# CPU.net
KiCad netlist of a schematic drawn in Altium Designer
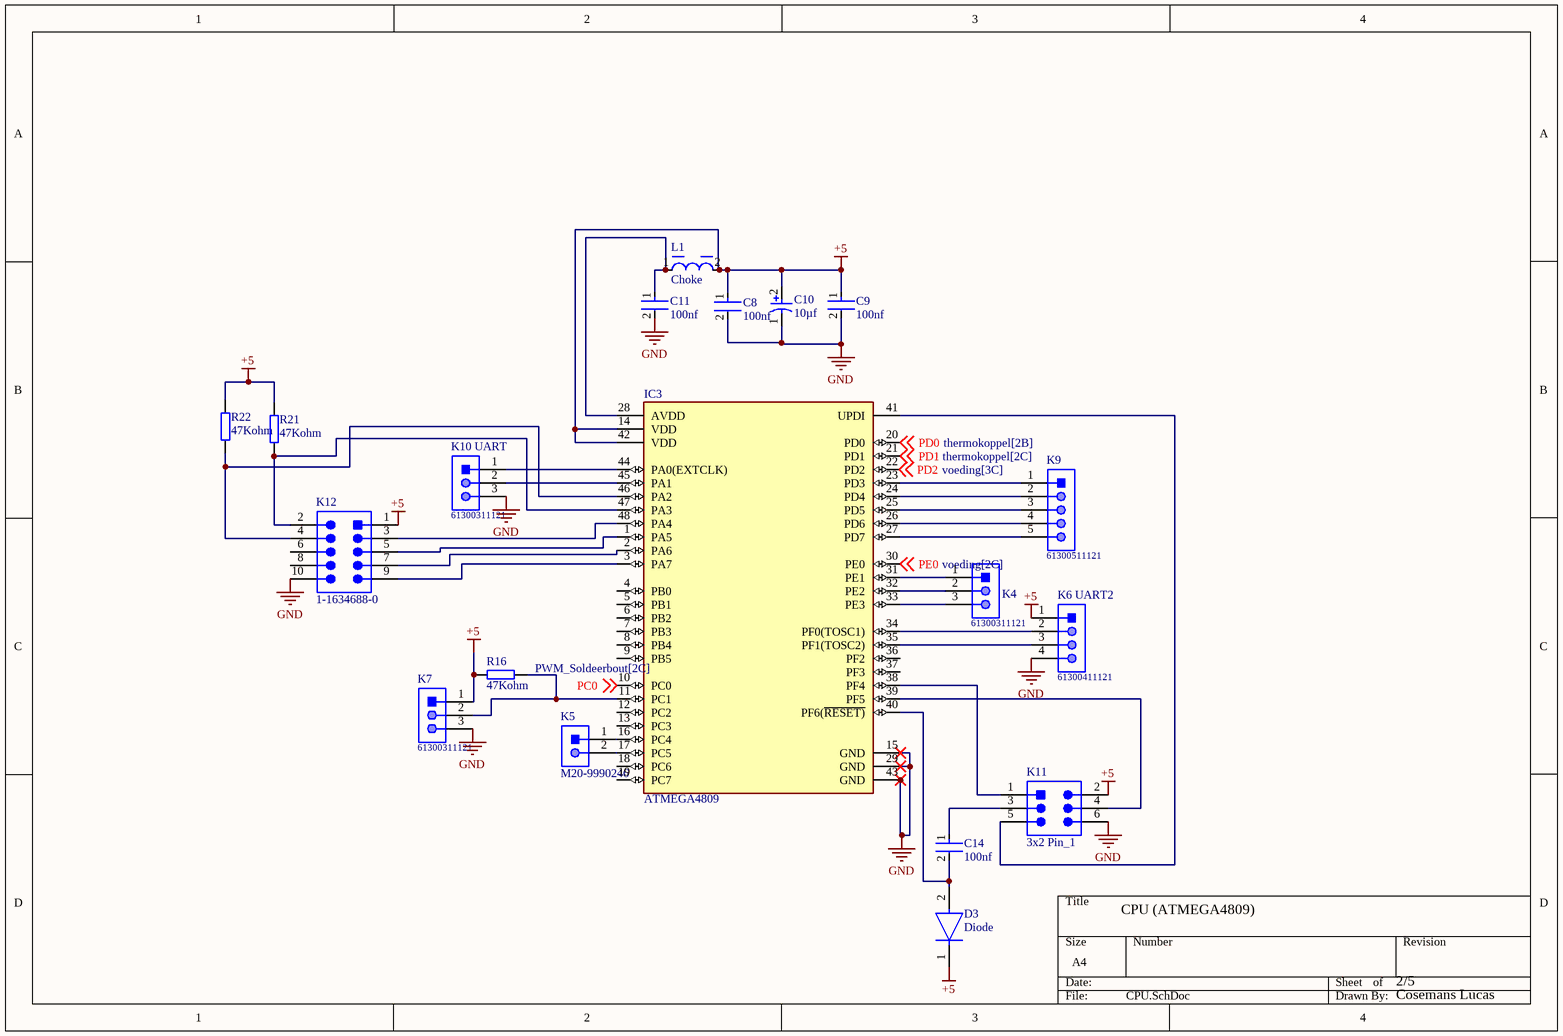
[diagram p0: CPU.SchDoc]

(export (version "E")
  (design (tool "Eeschema 10.0.6"))
  (components
    (comp (ref "C8")
      (value "100nf")
      (footprint "CC_0805_L")
      (fields
        (field (name "MANUFACTURER") "KEMET")
        (field (name "OCTOPART") "https://octopart.com/c0805c224k5ractu-kemet-144670")
        (field (name "MANUFACTURER PART NUMBER") "C0805C224K5RACTU")
      )
      (libsource (lib "Schematic_soldeerstation") (part "Capacitor_Ceramic"))
    )
    (comp (ref "C9")
      (value "100nf")
      (footprint "CC_0805_L")
      (fields
        (field (name "MANUFACTURER") "KEMET")
        (field (name "OCTOPART") "https://octopart.com/c0805c224k5ractu-kemet-144670")
        (field (name "MANUFACTURER PART NUMBER") "C0805C224K5RACTU")
      )
      (libsource (lib "Schematic_soldeerstation") (part "Capacitor_Ceramic"))
    )
    (comp (ref "C10")
      (value "10µf")
      (footprint "CE_D6,3_L4,5")
      (fields (field (name "MANUFACTURER") "Panasonic"))
      (libsource (lib "Schematic_soldeerstation") (part "Capacitor_Electrolytic"))
    )
    (comp (ref "C11")
      (value "100nf")
      (footprint "CC_0805_L")
      (fields
        (field (name "MANUFACTURER") "KEMET")
        (field (name "OCTOPART") "https://octopart.com/c0805c224k5ractu-kemet-144670")
        (field (name "MANUFACTURER PART NUMBER") "C0805C224K5RACTU")
      )
      (libsource (lib "Schematic_soldeerstation") (part "Capacitor_Ceramic"))
    )
    (comp (ref "C14")
      (value "100nf")
      (footprint "CC_0805_L")
      (fields
        (field (name "MANUFACTURER") "KEMET")
        (field (name "OCTOPART") "https://octopart.com/c0805c224k5ractu-kemet-144670")
        (field (name "MANUFACTURER PART NUMBER") "C0805C224K5RACTU")
      )
      (libsource (lib "Schematic_soldeerstation") (part "Capacitor_Ceramic"))
    )
    (comp (ref "D3")
      (value "Diode")
      (footprint "SOD-123FL")
      (fields
        (field (name "MANUFACTURER PART NUMBER") "1N4007")
        (field (name "MANUFACTURER") "Diotec")
        (field (name "OCTOPART") "https://octopart.com/1n4007-diotec-4040411")
      )
      (libsource (lib "Schematic_soldeerstation") (part "Diode"))
    )
    (comp (ref "IC3")
      (value "ATMEGA4809")
      (footprint "TQFP_48_M")
      (libsource (lib "Schematic_soldeerstation") (part "ATMEGA4809"))
    )
    (comp (ref "K4")
      (value "61300311121")
      (footprint "3x1 pin")
      (description "THT Vertical Pin Header WR-PHD, Pitch 2.54 mm, Single Row, 3 pins")
      (fields (field (name "MANUFACTURER") "Wurth Elektronik") (field (name "PUBLISHER") "WurthElektronik"))
      (libsource (lib "") (part "3x1 pin_1"))
    )
    (comp (ref "K5")
      (value "M20-9990246")
      (footprint "2x1 pin")
      (description "CONN HEADER VERT 2POS 2.54MM")
      (fields
        (field (name "OCTOPART") "https://octopart.com/m20-9990246-harwin-2590635")
        (field (name "MANUFACTURER") "Harwin")
      )
      (libsource (lib "Schematic_soldeerstation") (part "2x1 pin"))
    )
    (comp (ref "K6 UART2")
      (value "61300411121")
      (footprint "4x1 pin")
      (description "THT Vertical Pin Header WR-PHD, Pitch 2.54 mm, Single Row, 4 pins")
      (fields (field (name "MANUFACTURER") "Wurth Elektronik") (field (name "PUBLISHER") "WurthElektronik"))
      (libsource (lib "Schematic_soldeerstation") (part "4x1 pin"))
    )
    (comp (ref "K7")
      (value "61300311121")
      (footprint "3x1 pin")
      (description "THT Vertical Pin Header WR-PHD, Pitch 2.54 mm, Single Row, 3 pins")
      (fields (field (name "MANUFACTURER") "Wurth Elektronik") (field (name "PUBLISHER") "WurthElektronik"))
      (libsource (lib "Schematic_soldeerstation") (part "3x1 pin"))
    )
    (comp (ref "K9")
      (value "61300511121")
      (footprint "5x1 pin")
      (description "THT Vertical Pin Header WR-PHD, Pitch 2.54 mm, Single Row, 5 pins")
      (fields (field (name "MANUFACTURER") "Wurth Elektronik") (field (name "PUBLISHER") "WurthElektronik"))
      (libsource (lib "Schematic_soldeerstation") (part "5x1 pin"))
    )
    (comp (ref "K10 UART")
      (value "61300311121")
      (footprint "3x1 pin")
      (description "THT Vertical Pin Header WR-PHD, Pitch 2.54 mm, Single Row, 3 pins")
      (fields (field (name "MANUFACTURER") "Wurth Elektronik") (field (name "PUBLISHER") "WurthElektronik"))
      (libsource (lib "Schematic_soldeerstation") (part "3x1 pin"))
    )
    (comp (ref "K11")
      (value "3x2 Pin_1")
      (footprint "3x2 pin FP-M20-9980346-MFG")
      (libsource (lib "Schematic_soldeerstation") (part "3x2 Pin_1"))
    )
    (comp (ref "K12")
      (value "1-1634688-0")
      (footprint "5x2 pin - TECO-1-1634688-0-10_V")
      (fields (field (name "MANUFACTURER") "TE Connectivity"))
      (libsource (lib "Schematic_soldeerstation") (part "5x2 Pin"))
    )
    (comp (ref "L1")
      (value "Choke")
      (footprint "CC_0805_L")
      (fields (field (name "TOLERANCE") "20%"))
      (libsource (lib "Schematic_soldeerstation") (part "Choke"))
    )
    (comp (ref "R16")
      (value "47Kohm")
      (footprint "R_0805_M")
      (fields (field (name "MANUFACTURER") "Vishay Dale") (field (name "PART NUMBER") "CRCW08050000Z0EA"))
      (libsource (lib "Schematic_soldeerstation") (part "Resistor"))
    )
    (comp (ref "R21")
      (value "47Kohm")
      (footprint "R_0805_M")
      (fields (field (name "MANUFACTURER") "Vishay Dale") (field (name "PART NUMBER") "CRCW08050000Z0EA"))
      (libsource (lib "Schematic_soldeerstation") (part "Resistor"))
    )
    (comp (ref "R22")
      (value "47Kohm")
      (footprint "R_0805_M")
      (fields (field (name "MANUFACTURER") "Vishay Dale") (field (name "PART NUMBER") "CRCW08050000Z0EA"))
      (libsource (lib "Schematic_soldeerstation") (part "Resistor"))
    )
  )
  (nets
    (net (code "1") (name "+5") (class "Default")
      (node (ref "C10") (pin "2") (pinfunction "2_2") (pintype "passive"))
      (node (ref "C8") (pin "1") (pinfunction "1_1") (pintype "passive"))
      (node (ref "C9") (pin "1") (pinfunction "1_1") (pintype "passive"))
      (node (ref "D3") (pin "1") (pinfunction "C_1") (pintype "passive"))
      (node (ref "IC3") (pin "14") (pinfunction "VDD_14") (pintype "power_in"))
      (node (ref "IC3") (pin "42") (pinfunction "VDD_42") (pintype "power_in"))
      (node (ref "K11") (pin "2") (pinfunction "2_2") (pintype "passive"))
      (node (ref "K12") (pin "1") (pinfunction "1_1") (pintype "passive"))
      (node (ref "K6 UART2") (pin "1") (pinfunction "1_1") (pintype "passive"))
      (node (ref "K7") (pin "1") (pinfunction "1_1") (pintype "passive"))
      (node (ref "L1") (pin "2") (pinfunction "2_2") (pintype "passive"))
      (node (ref "R16") (pin "1") (pinfunction "1_1") (pintype "passive"))
      (node (ref "R21") (pin "1") (pinfunction "1_1") (pintype "passive"))
      (node (ref "R22") (pin "1") (pinfunction "1_1") (pintype "passive"))
    )
    (net (code "2") (name "GND") (class "Default")
      (node (ref "C10") (pin "1") (pinfunction "1_1") (pintype "passive"))
      (node (ref "C11") (pin "2") (pinfunction "2_2") (pintype "passive"))
      (node (ref "C8") (pin "2") (pinfunction "2_2") (pintype "passive"))
      (node (ref "C9") (pin "2") (pinfunction "2_2") (pintype "passive"))
      (node (ref "IC3") (pin "15") (pinfunction "GND_15") (pintype "open_emitter"))
      (node (ref "IC3") (pin "29") (pinfunction "GND_29") (pintype "power_in"))
      (node (ref "IC3") (pin "43") (pinfunction "GND_43") (pintype "power_in"))
      (node (ref "K10 UART") (pin "3") (pinfunction "3_3") (pintype "passive"))
      (node (ref "K11") (pin "6") (pinfunction "6_6") (pintype "passive"))
      (node (ref "K12") (pin "10") (pinfunction "10_10") (pintype "passive"))
      (node (ref "K6 UART2") (pin "4") (pinfunction "4_4") (pintype "passive"))
      (node (ref "K7") (pin "3") (pinfunction "3_3") (pintype "passive"))
    )
    (net (code "3") (name "Net-(C14-Pad1)") (class "Default")
      (node (ref "C14") (pin "1") (pinfunction "1_1") (pintype "passive"))
      (node (ref "K11") (pin "3") (pinfunction "3_3") (pintype "passive"))
    )
    (net (code "4") (name "Net-(D3-A)") (class "Default")
      (node (ref "C14") (pin "2") (pinfunction "2_2") (pintype "passive"))
      (node (ref "D3") (pin "2") (pinfunction "A_2") (pintype "passive"))
      (node (ref "IC3") (pin "40") (pinfunction "PF6(~{RESET)}_40") (pintype "bidirectional"))
    )
    (net (code "5") (name "Net-(IC3-AVDD)") (class "Default")
      (node (ref "C11") (pin "1") (pinfunction "1_1") (pintype "passive"))
      (node (ref "IC3") (pin "28") (pinfunction "AVDD_28") (pintype "power_in"))
      (node (ref "L1") (pin "1") (pinfunction "1_1") (pintype "passive"))
    )
    (net (code "6") (name "Net-(IC3-PA0(EXTCLK))") (class "Default")
      (node (ref "IC3") (pin "44") (pinfunction "PA0(EXTCLK)_44") (pintype "bidirectional"))
      (node (ref "K10 UART") (pin "1") (pinfunction "1_1") (pintype "passive"))
    )
    (net (code "7") (name "Net-(IC3-PA1)") (class "Default")
      (node (ref "IC3") (pin "45") (pinfunction "PA1_45") (pintype "bidirectional"))
      (node (ref "K10 UART") (pin "2") (pinfunction "2_2") (pintype "passive"))
    )
    (net (code "8") (name "Net-(IC3-PA2)") (class "Default")
      (node (ref "IC3") (pin "46") (pinfunction "PA2_46") (pintype "bidirectional"))
      (node (ref "K12") (pin "4") (pinfunction "4_4") (pintype "passive"))
      (node (ref "R22") (pin "2") (pinfunction "2_2") (pintype "passive"))
    )
    (net (code "9") (name "Net-(IC3-PA3)") (class "Default")
      (node (ref "IC3") (pin "47") (pinfunction "PA3_47") (pintype "bidirectional"))
      (node (ref "K12") (pin "2") (pinfunction "2_2") (pintype "passive"))
      (node (ref "R21") (pin "2") (pinfunction "2_2") (pintype "passive"))
    )
    (net (code "10") (name "Net-(IC3-PA4)") (class "Default")
      (node (ref "IC3") (pin "48") (pinfunction "PA4_48") (pintype "bidirectional"))
      (node (ref "K12") (pin "3") (pinfunction "3_3") (pintype "passive"))
    )
    (net (code "11") (name "Net-(IC3-PA5)") (class "Default")
      (node (ref "IC3") (pin "1") (pinfunction "PA5_1") (pintype "bidirectional"))
      (node (ref "K12") (pin "5") (pinfunction "5_5") (pintype "passive"))
    )
    (net (code "12") (name "Net-(IC3-PA6)") (class "Default")
      (node (ref "IC3") (pin "2") (pinfunction "PA6_2") (pintype "bidirectional"))
      (node (ref "K12") (pin "7") (pinfunction "7_7") (pintype "passive"))
    )
    (net (code "13") (name "Net-(IC3-PA7)") (class "Default")
      (node (ref "IC3") (pin "3") (pinfunction "PA7_3") (pintype "bidirectional"))
      (node (ref "K12") (pin "9") (pinfunction "9_9") (pintype "passive"))
    )
    (net (code "14") (name "Net-(IC3-PC1)") (class "Default")
      (node (ref "IC3") (pin "11") (pinfunction "PC1_11") (pintype "bidirectional"))
      (node (ref "K7") (pin "2") (pinfunction "2_2") (pintype "passive"))
      (node (ref "R16") (pin "2") (pinfunction "2_2") (pintype "passive"))
    )
    (net (code "15") (name "Net-(IC3-PC4)") (class "Default")
      (node (ref "IC3") (pin "16") (pinfunction "PC4_16") (pintype "bidirectional"))
      (node (ref "K5") (pin "1") (pinfunction "1_1") (pintype "passive"))
    )
    (net (code "16") (name "Net-(IC3-PC5)") (class "Default")
      (node (ref "IC3") (pin "17") (pinfunction "PC5_17") (pintype "bidirectional"))
      (node (ref "K5") (pin "2") (pinfunction "2_2") (pintype "passive"))
    )
    (net (code "17") (name "Net-(IC3-PD3)") (class "Default")
      (node (ref "IC3") (pin "23") (pinfunction "PD3_23") (pintype "bidirectional"))
      (node (ref "K9") (pin "1") (pinfunction "1_1") (pintype "passive"))
    )
    (net (code "18") (name "Net-(IC3-PD4)") (class "Default")
      (node (ref "IC3") (pin "24") (pinfunction "PD4_24") (pintype "bidirectional"))
      (node (ref "K9") (pin "2") (pinfunction "2_2") (pintype "passive"))
    )
    (net (code "19") (name "Net-(IC3-PD5)") (class "Default")
      (node (ref "IC3") (pin "25") (pinfunction "PD5_25") (pintype "bidirectional"))
      (node (ref "K9") (pin "3") (pinfunction "3_3") (pintype "passive"))
    )
    (net (code "20") (name "Net-(IC3-PD6)") (class "Default")
      (node (ref "IC3") (pin "26") (pinfunction "PD6_26") (pintype "bidirectional"))
      (node (ref "K9") (pin "4") (pinfunction "4_4") (pintype "passive"))
    )
    (net (code "21") (name "Net-(IC3-PD7)") (class "Default")
      (node (ref "IC3") (pin "27") (pinfunction "PD7_27") (pintype "bidirectional"))
      (node (ref "K9") (pin "5") (pinfunction "5_5") (pintype "passive"))
    )
    (net (code "22") (name "Net-(IC3-PE1)") (class "Default")
      (node (ref "IC3") (pin "31") (pinfunction "PE1_31") (pintype "bidirectional"))
      (node (ref "K4") (pin "1") (pinfunction "1_1") (pintype "passive"))
    )
    (net (code "23") (name "Net-(IC3-PE2)") (class "Default")
      (node (ref "IC3") (pin "32") (pinfunction "PE2_32") (pintype "bidirectional"))
      (node (ref "K4") (pin "2") (pinfunction "2_2") (pintype "passive"))
    )
    (net (code "24") (name "Net-(IC3-PE3)") (class "Default")
      (node (ref "IC3") (pin "33") (pinfunction "PE3_33") (pintype "bidirectional"))
      (node (ref "K4") (pin "3") (pinfunction "3_3") (pintype "passive"))
    )
    (net (code "25") (name "Net-(IC3-PF0(TOSC1))") (class "Default")
      (node (ref "IC3") (pin "34") (pinfunction "PF0(TOSC1)_34") (pintype "bidirectional"))
      (node (ref "K6 UART2") (pin "2") (pinfunction "2_2") (pintype "passive"))
    )
    (net (code "26") (name "Net-(IC3-PF1(TOSC2))") (class "Default")
      (node (ref "IC3") (pin "35") (pinfunction "PF1(TOSC2)_35") (pintype "bidirectional"))
      (node (ref "K6 UART2") (pin "3") (pinfunction "3_3") (pintype "passive"))
    )
    (net (code "27") (name "Net-(IC3-PF4)") (class "Default")
      (node (ref "IC3") (pin "38") (pinfunction "PF4_38") (pintype "bidirectional"))
      (node (ref "K11") (pin "1") (pinfunction "1_1") (pintype "passive"))
    )
    (net (code "28") (name "Net-(IC3-PF5)") (class "Default")
      (node (ref "IC3") (pin "39") (pinfunction "PF5_39") (pintype "bidirectional"))
      (node (ref "K11") (pin "4") (pinfunction "4_4") (pintype "passive"))
    )
    (net (code "29") (name "Net-(IC3-UPDI)") (class "Default")
      (node (ref "IC3") (pin "41") (pinfunction "UPDI_41") (pintype "passive"))
      (node (ref "K11") (pin "5") (pinfunction "5_5") (pintype "passive"))
    )
    (net (code "30") (name "PC0") (class "Default")
      (node (ref "IC3") (pin "10") (pinfunction "PC0_10") (pintype "bidirectional"))
    )
    (net (code "31") (name "PD0") (class "Default")
      (node (ref "IC3") (pin "20") (pinfunction "PD0_20") (pintype "bidirectional"))
    )
    (net (code "32") (name "PD1") (class "Default")
      (node (ref "IC3") (pin "21") (pinfunction "PD1_21") (pintype "bidirectional"))
    )
    (net (code "34") (name "PE0") (class "Default")
      (node (ref "IC3") (pin "30") (pinfunction "PE0_30") (pintype "bidirectional"))
    )
    (net (code "35") (name "unconnected-(IC3-PB0-Pad4)") (class "Default")
      (node (ref "IC3") (pin "4") (pinfunction "PB0_4") (pintype "bidirectional"))
    )
    (net (code "36") (name "unconnected-(IC3-PB1-Pad5)") (class "Default")
      (node (ref "IC3") (pin "5") (pinfunction "PB1_5") (pintype "bidirectional"))
    )
    (net (code "37") (name "unconnected-(IC3-PB2-Pad6)") (class "Default")
      (node (ref "IC3") (pin "6") (pinfunction "PB2_6") (pintype "bidirectional"))
    )
    (net (code "38") (name "unconnected-(IC3-PB3-Pad7)") (class "Default")
      (node (ref "IC3") (pin "7") (pinfunction "PB3_7") (pintype "bidirectional"))
    )
    (net (code "39") (name "unconnected-(IC3-PB4-Pad8)") (class "Default")
      (node (ref "IC3") (pin "8") (pinfunction "PB4_8") (pintype "bidirectional"))
    )
    (net (code "40") (name "unconnected-(IC3-PB5-Pad9)") (class "Default")
      (node (ref "IC3") (pin "9") (pinfunction "PB5_9") (pintype "bidirectional"))
    )
    (net (code "41") (name "unconnected-(IC3-PC2-Pad12)") (class "Default")
      (node (ref "IC3") (pin "12") (pinfunction "PC2_12") (pintype "bidirectional"))
    )
    (net (code "42") (name "unconnected-(IC3-PC3-Pad13)") (class "Default")
      (node (ref "IC3") (pin "13") (pinfunction "PC3_13") (pintype "bidirectional"))
    )
    (net (code "43") (name "unconnected-(IC3-PC6-Pad18)") (class "Default")
      (node (ref "IC3") (pin "18") (pinfunction "PC6_18") (pintype "bidirectional"))
    )
    (net (code "44") (name "unconnected-(IC3-PC7-Pad19)") (class "Default")
      (node (ref "IC3") (pin "19") (pinfunction "PC7_19") (pintype "bidirectional"))
    )
    (net (code "45") (name "unconnected-(IC3-PD2-Pad22)") (class "Default")
      (node (ref "IC3") (pin "22") (pinfunction "PD2_22") (pintype "bidirectional"))
    )
    (net (code "46") (name "unconnected-(IC3-PF2-Pad36)") (class "Default")
      (node (ref "IC3") (pin "36") (pinfunction "PF2_36") (pintype "bidirectional"))
    )
    (net (code "47") (name "unconnected-(IC3-PF3-Pad37)") (class "Default")
      (node (ref "IC3") (pin "37") (pinfunction "PF3_37") (pintype "bidirectional"))
    )
    (net (code "48") (name "unconnected-(K12-Pad6)") (class "Default")
      (node (ref "K12") (pin "6") (pinfunction "6_6") (pintype "passive"))
    )
    (net (code "49") (name "unconnected-(K12-Pad8)") (class "Default")
      (node (ref "K12") (pin "8") (pinfunction "8_8") (pintype "passive"))
    )
  )
)
